# NCP346.net
KiCad netlist of a schematic drawn in EAGLE
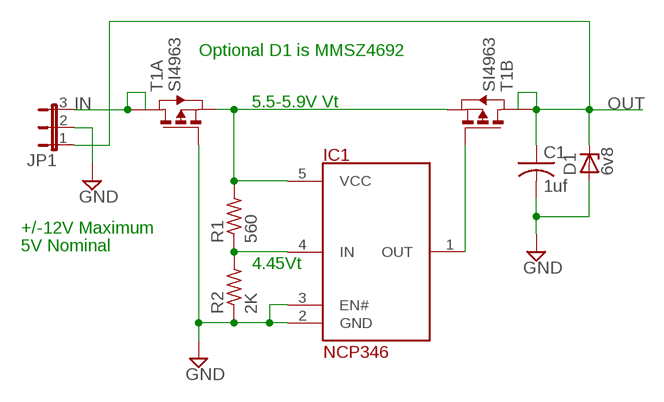
[diagram p0: schematic, sheet 1]

(export (version "E")
  (design (tool "Eeschema 10.0.6"))
  (components
    (comp (ref "C1")
      (value "1uf")
      (footprint "eagle-import:C1206")
      (libsource (lib "eagle-import") (part "C-USC1206"))
    )
    (comp (ref "D1")
      (value "6v8")
      (footprint "eagle-import:SOD80C")
      (libsource (lib "eagle-import") (part "ZENER-DIODESOD80C"))
    )
    (comp (ref "IC1")
      (value "NCP346")
      (footprint "eagle-import:SOT23-5")
      (libsource (lib "eagle-import") (part "NCP346"))
    )
    (comp (ref "JP1")
      (value "JP2W")
      (footprint "eagle-import:JP2W")
      (libsource (lib "eagle-import") (part "JP2W"))
    )
    (comp (ref "R1")
      (value "560")
      (footprint "eagle-import:R0603")
      (libsource (lib "eagle-import") (part "R-US_R0603"))
    )
    (comp (ref "R2")
      (value "2K")
      (footprint "eagle-import:R0603")
      (libsource (lib "eagle-import") (part "R-US_R0603"))
    )
    (comp (ref "T1")
      (value "SI4963")
      (footprint "eagle-import:SO8")
      (libsource (lib "eagle-import") (part "SI4963"))
    )
  )
  (nets
    (net (code "1") (name "/IN") (class "Default")
      (node (ref "JP1") (pin "3") (pinfunction "3_3") (pintype "passive"))
      (node (ref "T1") (pin "5") (pinfunction "D_5") (pintype "passive"))
      (node (ref "T1") (pin "6") (pinfunction "D1_6") (pintype "passive"))
    )
    (net (code "2") (name "/OUT") (class "Default")
      (node (ref "C1") (pin "1") (pinfunction "1_1") (pintype "passive"))
      (node (ref "D1") (pin "C") (pinfunction "C_C") (pintype "passive"))
      (node (ref "JP1") (pin "1") (pinfunction "1_1") (pintype "passive"))
      (node (ref "T1") (pin "7") (pinfunction "D_7") (pintype "passive"))
      (node (ref "T1") (pin "8") (pinfunction "D1_8") (pintype "passive"))
    )
    (net (code "3") (name "GND") (class "Default")
      (node (ref "C1") (pin "2") (pinfunction "2_2") (pintype "passive"))
      (node (ref "D1") (pin "A") (pinfunction "A_A") (pintype "passive"))
      (node (ref "IC1") (pin "2") (pinfunction "GND_2") (pintype "power_in"))
      (node (ref "IC1") (pin "3") (pinfunction "EN#_3") (pintype "input"))
      (node (ref "JP1") (pin "2") (pinfunction "2_2") (pintype "passive"))
      (node (ref "R2") (pin "1") (pinfunction "1_1") (pintype "passive"))
      (node (ref "T1") (pin "4") (pinfunction "G_4") (pintype "passive"))
    )
    (net (code "4") (name "Net-(IC1-IN)") (class "Default")
      (node (ref "IC1") (pin "4") (pinfunction "IN_4") (pintype "input"))
      (node (ref "R1") (pin "1") (pinfunction "1_1") (pintype "passive"))
      (node (ref "R2") (pin "2") (pinfunction "2_2") (pintype "passive"))
    )
    (net (code "5") (name "Net-(IC1-OUT)") (class "Default")
      (node (ref "IC1") (pin "1") (pinfunction "OUT_1") (pintype "output"))
      (node (ref "T1") (pin "2") (pinfunction "G_2") (pintype "passive"))
    )
    (net (code "6") (name "Net-(IC1-VCC)") (class "Default")
      (node (ref "IC1") (pin "5") (pinfunction "VCC_5") (pintype "power_in"))
      (node (ref "R1") (pin "2") (pinfunction "2_2") (pintype "passive"))
      (node (ref "T1") (pin "1") (pinfunction "S_1") (pintype "passive"))
      (node (ref "T1") (pin "3") (pinfunction "S_3") (pintype "passive"))
    )
  )
)
